# CH340-3V-smd.net
KiCad netlist of a schematic drawn in EAGLE
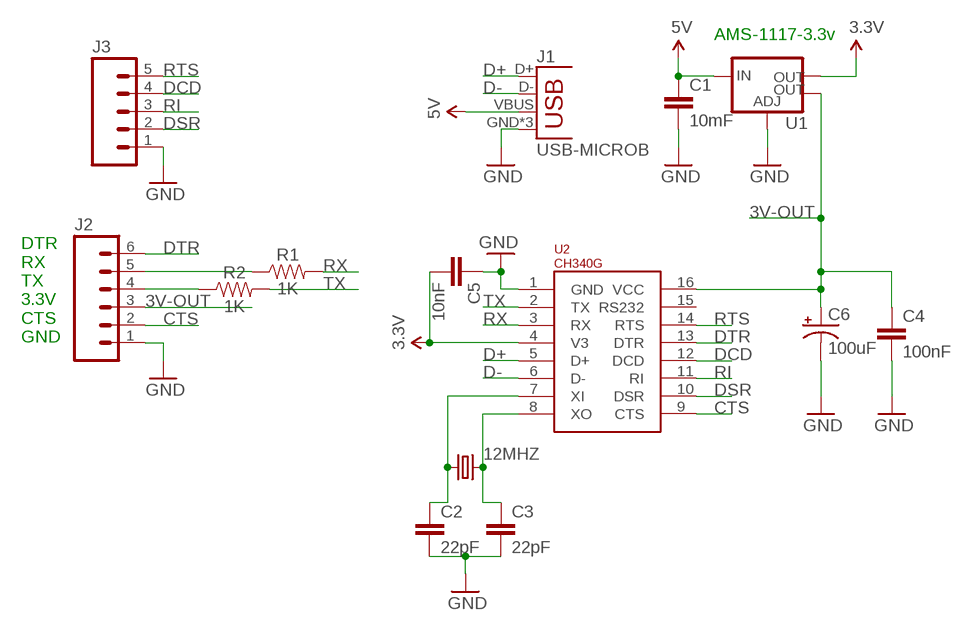
[diagram p0: schematic, sheet 1]

(export (version "E")
  (design (tool "Eeschema 10.0.6"))
  (components
    (comp (ref "12MHZ")
      (value "CRYSTALHC49US")
      (footprint "eagle-import:HC49US")
      (libsource (lib "eagle-import") (part "CRYSTALHC49US"))
    )
    (comp (ref "C1")
      (value "10mF")
      (footprint "eagle-import:0805")
      (libsource (lib "eagle-import") (part "CAP0805"))
    )
    (comp (ref "C2")
      (value "22pF")
      (footprint "eagle-import:1206")
      (libsource (lib "eagle-import") (part "CAP-NONPOLAR1206"))
    )
    (comp (ref "C3")
      (value "22pF")
      (footprint "eagle-import:1206")
      (libsource (lib "eagle-import") (part "CAP-NONPOLAR1206"))
    )
    (comp (ref "C4")
      (value "100nF")
      (footprint "eagle-import:1206")
      (libsource (lib "eagle-import") (part "CAP1206"))
    )
    (comp (ref "C5")
      (value "10nF")
      (footprint "eagle-import:1206")
      (libsource (lib "eagle-import") (part "CAP1206"))
    )
    (comp (ref "C6")
      (value "100uF")
      (footprint "eagle-import:EIA3528")
      (libsource (lib "eagle-import") (part "10UF-POLAR-EIA3528-20V-10%(TANT)"))
    )
    (comp (ref "J1")
      (value "USB-MICROB")
      (footprint "eagle-import:USB-MICROB")
      (libsource (lib "eagle-import") (part "USB-MICROB"))
    )
    (comp (ref "J2")
      (value "M06SILK_FEMALE_PTH")
      (footprint "eagle-import:1X06")
      (libsource (lib "eagle-import") (part "M06SILK_FEMALE_PTH"))
    )
    (comp (ref "J3")
      (value "M05PTH")
      (footprint "eagle-import:1X05")
      (libsource (lib "eagle-import") (part "M05PTH"))
    )
    (comp (ref "R1")
      (value "1K")
      (footprint "eagle-import:0805")
      (libsource (lib "eagle-import") (part "RESISTOR0805"))
    )
    (comp (ref "R2")
      (value "1K")
      (footprint "eagle-import:0805")
      (libsource (lib "eagle-import") (part "RESISTOR0805"))
    )
    (comp (ref "U1")
      (value "V_REG_LM1117SOT223")
      (footprint "eagle-import:SOT223")
      (libsource (lib "eagle-import") (part "V_REG_LM1117SOT223"))
    )
    (comp (ref "U2")
      (value "CH340G")
      (footprint "eagle-import:SOIC16")
      (libsource (lib "eagle-import") (part "CH340G"))
    )
  )
  (nets
    (net (code "1") (name "/3V-OUT") (class "Default")
      (node (ref "C4") (pin "1") (pinfunction "1_1") (pintype "passive"))
      (node (ref "C6") (pin "A") (pinfunction "+_A") (pintype "passive"))
      (node (ref "J2") (pin "3") (pinfunction "3_3") (pintype "passive"))
      (node (ref "U1") (pin "4") (pinfunction "OUT_4") (pintype "output"))
      (node (ref "U2") (pin "16") (pinfunction "VCC_16") (pintype "bidirectional"))
    )
    (net (code "2") (name "/CTS") (class "Default")
      (node (ref "J2") (pin "2") (pinfunction "2_2") (pintype "passive"))
      (node (ref "U2") (pin "9") (pinfunction "CTS_9") (pintype "bidirectional"))
    )
    (net (code "3") (name "/D+") (class "Default")
      (node (ref "J1") (pin "D+") (pinfunction "D+_D+") (pintype "bidirectional"))
      (node (ref "U2") (pin "5") (pinfunction "D+_5") (pintype "bidirectional"))
    )
    (net (code "4") (name "/D-") (class "Default")
      (node (ref "J1") (pin "D-") (pinfunction "D-_D-") (pintype "bidirectional"))
      (node (ref "U2") (pin "6") (pinfunction "D-_6") (pintype "bidirectional"))
    )
    (net (code "5") (name "/DCD") (class "Default")
      (node (ref "J3") (pin "4") (pinfunction "4_4") (pintype "passive"))
      (node (ref "U2") (pin "12") (pinfunction "DCD_12") (pintype "bidirectional"))
    )
    (net (code "6") (name "/DSR") (class "Default")
      (node (ref "J3") (pin "2") (pinfunction "2_2") (pintype "passive"))
      (node (ref "U2") (pin "10") (pinfunction "DSR_10") (pintype "bidirectional"))
    )
    (net (code "7") (name "/DTR") (class "Default")
      (node (ref "J2") (pin "6") (pinfunction "6_6") (pintype "passive"))
      (node (ref "U2") (pin "13") (pinfunction "DTR_13") (pintype "bidirectional"))
    )
    (net (code "8") (name "/RI") (class "Default")
      (node (ref "J3") (pin "3") (pinfunction "3_3") (pintype "passive"))
      (node (ref "U2") (pin "11") (pinfunction "RI_11") (pintype "bidirectional"))
    )
    (net (code "9") (name "/RTS") (class "Default")
      (node (ref "J3") (pin "5") (pinfunction "5_5") (pintype "passive"))
      (node (ref "U2") (pin "14") (pinfunction "RTS_14") (pintype "bidirectional"))
    )
    (net (code "10") (name "/RX") (class "Default")
      (node (ref "R1") (pin "2") (pinfunction "2_2") (pintype "passive"))
      (node (ref "U2") (pin "3") (pinfunction "RX_3") (pintype "bidirectional"))
    )
    (net (code "11") (name "/TX") (class "Default")
      (node (ref "R2") (pin "2") (pinfunction "2_2") (pintype "passive"))
      (node (ref "U2") (pin "2") (pinfunction "TX_2") (pintype "bidirectional"))
    )
    (net (code "12") (name "3.3V") (class "Default")
      (node (ref "C5") (pin "2") (pinfunction "2_2") (pintype "passive"))
      (node (ref "U1") (pin "2") (pinfunction "OUT_2") (pintype "output"))
      (node (ref "U2") (pin "4") (pinfunction "V3_4") (pintype "bidirectional"))
    )
    (net (code "13") (name "5V") (class "Default")
      (node (ref "C1") (pin "1") (pinfunction "1_1") (pintype "passive"))
      (node (ref "J1") (pin "VBUS") (pinfunction "VBUS_VBUS") (pintype "bidirectional"))
      (node (ref "U1") (pin "3") (pinfunction "IN_3") (pintype "input"))
    )
    (net (code "14") (name "GND") (class "Default")
      (node (ref "C1") (pin "2") (pinfunction "2_2") (pintype "passive"))
      (node (ref "C2") (pin "2") (pinfunction "2_2") (pintype "passive"))
      (node (ref "C3") (pin "2") (pinfunction "2_2") (pintype "passive"))
      (node (ref "C4") (pin "2") (pinfunction "2_2") (pintype "passive"))
      (node (ref "C5") (pin "1") (pinfunction "1_1") (pintype "passive"))
      (node (ref "C6") (pin "C") (pinfunction "-_C") (pintype "passive"))
      (node (ref "J1") (pin "GND") (pinfunction "GND_GND") (pintype "bidirectional"))
      (node (ref "J1") (pin "MT1") (pinfunction "GND_MT1") (pintype "bidirectional"))
      (node (ref "J1") (pin "MT2") (pinfunction "GND_MT2") (pintype "bidirectional"))
      (node (ref "J2") (pin "1") (pinfunction "1_1") (pintype "passive"))
      (node (ref "J3") (pin "1") (pinfunction "1_1") (pintype "passive"))
      (node (ref "U1") (pin "1") (pinfunction "ADJ_1") (pintype "input"))
      (node (ref "U2") (pin "1") (pinfunction "GND_1") (pintype "bidirectional"))
    )
    (net (code "15") (name "Net-(J2-Pad4)") (class "Default")
      (node (ref "J2") (pin "4") (pinfunction "4_4") (pintype "passive"))
      (node (ref "R2") (pin "1") (pinfunction "1_1") (pintype "passive"))
    )
    (net (code "16") (name "Net-(J2-Pad5)") (class "Default")
      (node (ref "J2") (pin "5") (pinfunction "5_5") (pintype "passive"))
      (node (ref "R1") (pin "1") (pinfunction "1_1") (pintype "passive"))
    )
    (net (code "17") (name "Net-(U2-XI)") (class "Default")
      (node (ref "12MHZ") (pin "1") (pinfunction "1_1") (pintype "passive"))
      (node (ref "C2") (pin "1") (pinfunction "1_1") (pintype "passive"))
      (node (ref "U2") (pin "7") (pinfunction "XI_7") (pintype "bidirectional"))
    )
    (net (code "18") (name "Net-(U2-XO)") (class "Default")
      (node (ref "12MHZ") (pin "2") (pinfunction "2_2") (pintype "passive"))
      (node (ref "C3") (pin "1") (pinfunction "1_1") (pintype "passive"))
      (node (ref "U2") (pin "8") (pinfunction "XO_8") (pintype "bidirectional"))
    )
    (net (code "19") (name "unconnected-(U2-RS232-Pad15)") (class "Default")
      (node (ref "U2") (pin "15") (pinfunction "RS232_15") (pintype "bidirectional"))
    )
  )
)
